# BSPD_-_AMS.net
KiCad netlist of a schematic drawn in Altium Designer
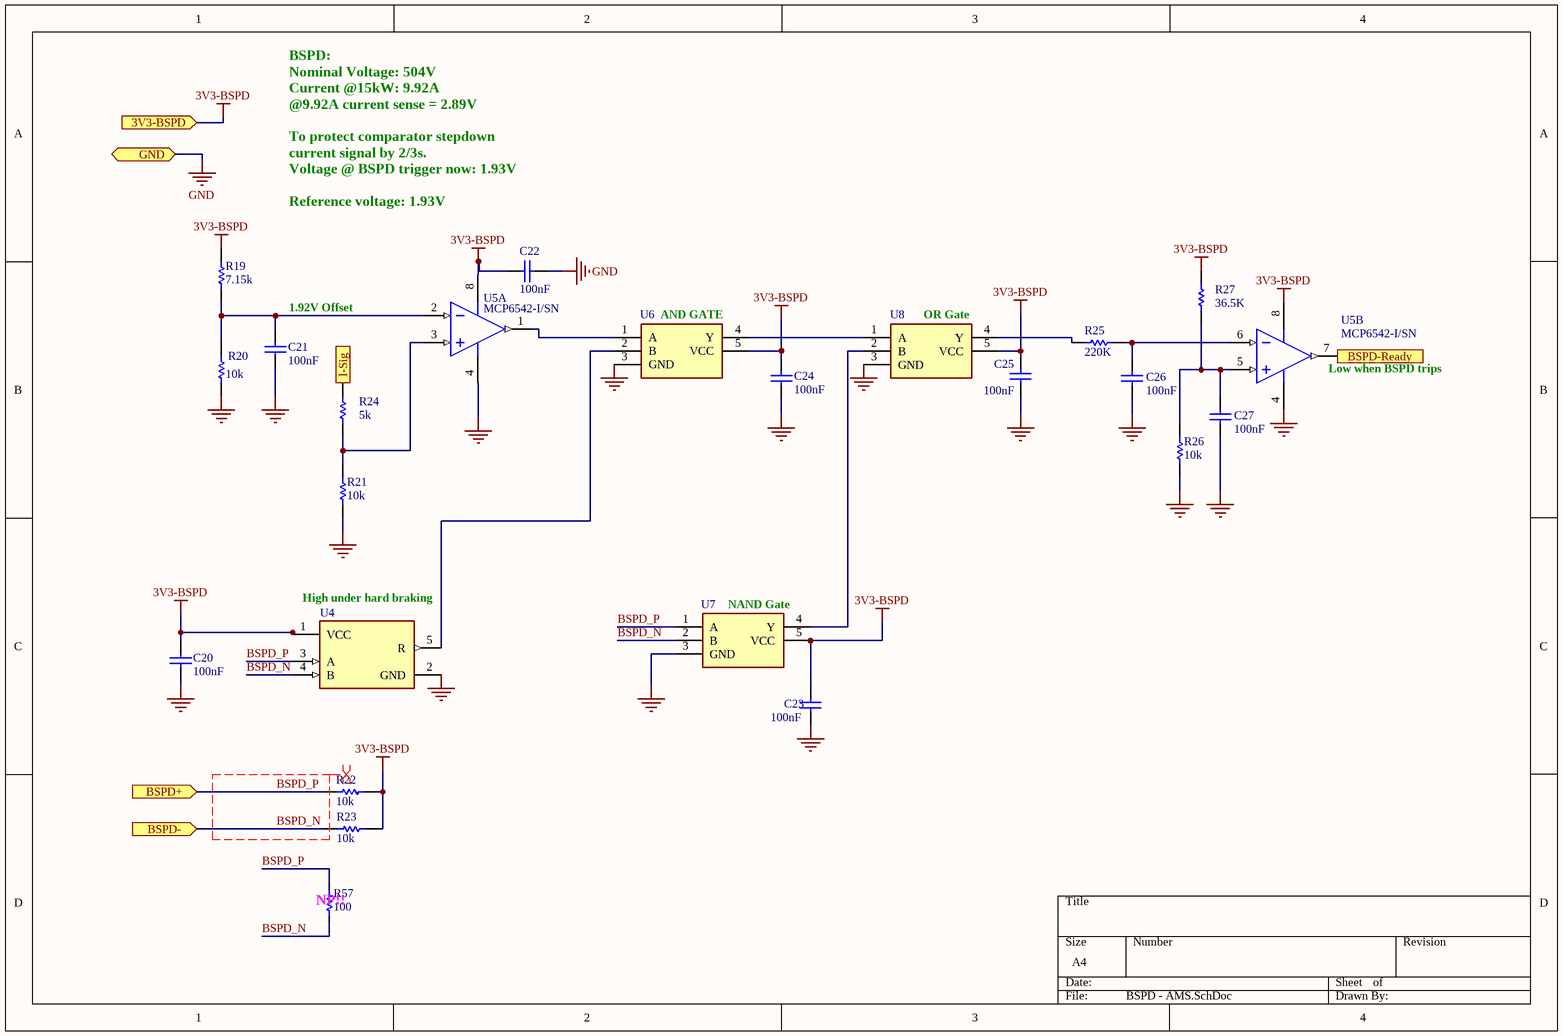
[diagram p0: BSPD - AMS.SchDoc]

(export (version "E")
  (design (tool "Eeschema 10.0.6"))
  (components
    (comp (ref "C20")
      (value "100nF")
      (footprint "CAP0603")
      (description "C0603C104K3RAC7013")
      (fields (field (name "PUBLISHER") "Altium Limited"))
      (libsource (lib "Miscellaneous Devices") (part "Cap"))
    )
    (comp (ref "C21")
      (value "100nF")
      (footprint "CAP0603")
      (description "C0603C104K3RAC7013")
      (fields (field (name "PUBLISHER") "Altium Limited"))
      (libsource (lib "Miscellaneous Devices") (part "Cap"))
    )
    (comp (ref "C22")
      (value "100nF")
      (footprint "CAP0603")
      (description "C0603C104K3RAC7013")
      (fields (field (name "PUBLISHER") "Altium Limited"))
      (libsource (lib "Miscellaneous Devices") (part "Cap"))
    )
    (comp (ref "C23")
      (value "100nF")
      (footprint "CAP0603")
      (description "C0603C104K3RAC7013")
      (fields (field (name "PUBLISHER") "Altium Limited"))
      (libsource (lib "Miscellaneous Devices") (part "Cap"))
    )
    (comp (ref "C24")
      (value "100nF")
      (footprint "CAP0603")
      (description "C0603C104K3RAC7013")
      (fields (field (name "PUBLISHER") "Altium Limited"))
      (libsource (lib "Miscellaneous Devices") (part "Cap"))
    )
    (comp (ref "C25")
      (value "100nF")
      (footprint "CAP0603")
      (description "C0603C104K3RAC7013")
      (fields (field (name "PUBLISHER") "Altium Limited"))
      (libsource (lib "Miscellaneous Devices") (part "Cap"))
    )
    (comp (ref "C26")
      (value "100nF")
      (footprint "CAP0603")
      (description "C0603C104K3RAC7013")
      (fields (field (name "PUBLISHER") "Altium Limited"))
      (libsource (lib "Miscellaneous Devices") (part "Cap"))
    )
    (comp (ref "C27")
      (value "100nF")
      (footprint "CAP0603")
      (description "C0603C104K3RAC7013")
      (fields (field (name "PUBLISHER") "Altium Limited"))
      (libsource (lib "Miscellaneous Devices") (part "Cap"))
    )
    (comp (ref "R19")
      (value "7.15k")
      (footprint "RESC1608X55N")
      (fields (field (name "Comment") "RN73C1J7K15BTDF") (field (name "PUBLISHER") "Altium Limited"))
      (libsource (lib "Miscellaneous Devices") (part "Res1"))
    )
    (comp (ref "R20")
      (value "10k")
      (footprint "RESC1608X55N")
      (fields (field (name "Comment") "RC0603FR-1310KL") (field (name "PUBLISHER") "Altium Limited"))
      (libsource (lib "Miscellaneous Devices") (part "Res1"))
    )
    (comp (ref "R21")
      (value "10k")
      (footprint "RESC1608X55N")
      (fields (field (name "Comment") "RC0603FR-1310KL") (field (name "PUBLISHER") "Altium Limited"))
      (libsource (lib "Miscellaneous Devices") (part "Res1"))
    )
    (comp (ref "R22")
      (value "10k")
      (footprint "RESC1608X55N")
      (description "169-4216")
      (fields (field (name "Comment") "RC0603FR-1310KL") (field (name "PUBLISHER") "Altium Limited"))
      (libsource (lib "Miscellaneous Devices") (part "Res1"))
    )
    (comp (ref "R23")
      (value "10k")
      (footprint "RESC1608X55N")
      (description "169-4216")
      (fields (field (name "Comment") "RC0603FR-1310KL") (field (name "PUBLISHER") "Altium Limited"))
      (libsource (lib "Miscellaneous Devices") (part "Res1"))
    )
    (comp (ref "R24")
      (value "5k")
      (footprint "RESC1608X55N")
      (fields (field (name "Comment") "CR0603AFX-5101EAS") (field (name "PUBLISHER") "Altium Limited"))
      (libsource (lib "Miscellaneous Devices") (part "Res1"))
    )
    (comp (ref "R25")
      (value "220K")
      (footprint "RESC1608X55N")
      (description "Resistor")
      (fields (field (name "Comment") "CRCW0603-220K-E3") (field (name "PUBLISHER") "Altium Limited"))
      (libsource (lib "Miscellaneous Devices") (part "Res1"))
    )
    (comp (ref "R26")
      (value "10k")
      (footprint "RESC1608X55N")
      (description "Resistor")
      (fields (field (name "Comment") "RC0603FR-1310KL") (field (name "PUBLISHER") "Altium Limited"))
      (libsource (lib "Miscellaneous Devices") (part "Res1"))
    )
    (comp (ref "R27")
      (value "36.5K")
      (footprint "RESC1608X55N")
      (description "Resistor")
      (fields (field (name "Comment") "CRCW060336K5FKEAC") (field (name "PUBLISHER") "Altium Limited"))
      (libsource (lib "Miscellaneous Devices") (part "Res1"))
    )
    (comp (ref "R57")
      (value "100")
      (footprint "R-0603")
      (description "NP")
      (fields (field (name "Comment") "Resistor"))
      (libsource (lib "Passives") (part "Resistor"))
    )
    (comp (ref "U4")
      (value "SN65LVDT2DBVT")
      (footprint "FP-DBV0005A-MFG")
      (description "IC RECEIVER 0/1 SOT23-5")
      (fields
        (field (name "OCTOPART") "https://octopart.com/sn65lvdt2dbvt-texas+instruments-712102")
        (field (name "MANUFACTURER") "Texas Instruments")
      )
      (libsource (lib "Altium Content Vault") (part "80154aa7be0093f96882e9a6708b811"))
    )
    (comp (ref "U5")
      (value "MCP6542-I/SN")
      (footprint "SOIC-SN8_N")
      (description "Push-Pull Output Sub-Microamp Comparator, 8-Pin SOIC, Industrial Temperature")
      (libsource (lib "Altium Content Vault") (part "LO-COMP-MCP6542-IL8"))
    )
    (comp (ref "U6")
      (value "SN74LVC1G08MDBVREP")
      (footprint "SOT95P280X145-5N")
      (description "Integrated Circuit")
      (fields (field (name "MOUSER2 PART NUMBER") "595-SN74LVC08MDBVREP"))
      (libsource (lib "SamacSys") (part "SN74LVC1G08MDBVREP"))
    )
    (comp (ref "U7")
      (value "NC7SZ00M5X")
      (footprint "SOT95P280X125-5N")
      (description "NAND GATEEE")
      (fields (field (name "MANUFACTURER_PART_NUMBER") "NC7S02M5X"))
      (libsource (lib "SamacSys") (part "NC7S02M5X"))
    )
    (comp (ref "U8")
      (value "NC7S32M5X")
      (footprint "SOT95P275X110-5N")
      (description "OR GATEEEE")
      (libsource (lib "SamacSys") (part "NC7S32M5X"))
    )
  )
  (nets
    (net (code "1") (name "/BSPD-Ready") (class "Default")
      (node (ref "U5") (pin "7") (pinfunction "OUTB_7") (pintype "output"))
    )
    (net (code "2") (name "/BSPD_N") (class "Default")
      (node (ref "R23") (pin "1") (pinfunction "1_1") (pintype "passive"))
      (node (ref "R57") (pin "1") (pinfunction "1_1") (pintype "passive"))
      (node (ref "U4") (pin "4") (pinfunction "B_4") (pintype "input"))
      (node (ref "U7") (pin "2") (pinfunction "B_2") (pintype "passive"))
    )
    (net (code "3") (name "/BSPD_P") (class "Default")
      (node (ref "R22") (pin "1") (pinfunction "1_1") (pintype "passive"))
      (node (ref "R57") (pin "2") (pinfunction "2_2") (pintype "passive"))
      (node (ref "U4") (pin "3") (pinfunction "A_3") (pintype "input"))
      (node (ref "U7") (pin "1") (pinfunction "A_1") (pintype "passive"))
    )
    (net (code "4") (name "/I-Sig") (class "Default")
      (node (ref "R24") (pin "2") (pinfunction "2_2") (pintype "passive"))
    )
    (net (code "5") (name "3V3-BSPD") (class "Default")
      (node (ref "C20") (pin "2") (pinfunction "2_2") (pintype "passive"))
      (node (ref "C22") (pin "2") (pinfunction "2_2") (pintype "passive"))
      (node (ref "C23") (pin "2") (pinfunction "2_2") (pintype "passive"))
      (node (ref "C24") (pin "2") (pinfunction "2_2") (pintype "passive"))
      (node (ref "C25") (pin "2") (pinfunction "2_2") (pintype "passive"))
      (node (ref "R19") (pin "2") (pinfunction "2_2") (pintype "passive"))
      (node (ref "R22") (pin "2") (pinfunction "2_2") (pintype "passive"))
      (node (ref "R23") (pin "2") (pinfunction "2_2") (pintype "passive"))
      (node (ref "R27") (pin "2") (pinfunction "2_2") (pintype "passive"))
      (node (ref "U4") (pin "1") (pinfunction "VCC_1") (pintype "passive"))
      (node (ref "U5") (pin "8") (pinfunction "VDD_8") (pintype "passive"))
      (node (ref "U6") (pin "5") (pinfunction "VCC_5") (pintype "passive"))
      (node (ref "U7") (pin "5") (pinfunction "VCC_5") (pintype "passive"))
      (node (ref "U8") (pin "5") (pinfunction "VCC_5") (pintype "passive"))
    )
    (net (code "6") (name "GND") (class "Default")
      (node (ref "C20") (pin "1") (pinfunction "1_1") (pintype "passive"))
      (node (ref "C21") (pin "1") (pinfunction "1_1") (pintype "passive"))
      (node (ref "C22") (pin "1") (pinfunction "1_1") (pintype "passive"))
      (node (ref "C23") (pin "1") (pinfunction "1_1") (pintype "passive"))
      (node (ref "C24") (pin "1") (pinfunction "1_1") (pintype "passive"))
      (node (ref "C25") (pin "1") (pinfunction "1_1") (pintype "passive"))
      (node (ref "C26") (pin "1") (pinfunction "1_1") (pintype "passive"))
      (node (ref "C27") (pin "1") (pinfunction "1_1") (pintype "passive"))
      (node (ref "R20") (pin "1") (pinfunction "1_1") (pintype "passive"))
      (node (ref "R21") (pin "1") (pinfunction "1_1") (pintype "passive"))
      (node (ref "R26") (pin "1") (pinfunction "1_1") (pintype "passive"))
      (node (ref "U4") (pin "2") (pinfunction "GND_2") (pintype "passive"))
      (node (ref "U5") (pin "4") (pinfunction "VSS_4") (pintype "power_in"))
      (node (ref "U6") (pin "3") (pinfunction "GND_3") (pintype "passive"))
      (node (ref "U7") (pin "3") (pinfunction "GND_3") (pintype "passive"))
      (node (ref "U8") (pin "3") (pinfunction "GND_3") (pintype "passive"))
    )
    (net (code "7") (name "Net-(U4-R)") (class "Default")
      (node (ref "U4") (pin "5") (pinfunction "R_5") (pintype "output"))
      (node (ref "U6") (pin "2") (pinfunction "B_2") (pintype "passive"))
    )
    (net (code "8") (name "Net-(U5A-OUTA)") (class "Default")
      (node (ref "U5") (pin "1") (pinfunction "OUTA_1") (pintype "output"))
      (node (ref "U6") (pin "1") (pinfunction "A_1") (pintype "passive"))
    )
    (net (code "9") (name "Net-(U5A-VINA+)") (class "Default")
      (node (ref "R21") (pin "2") (pinfunction "2_2") (pintype "passive"))
      (node (ref "R24") (pin "1") (pinfunction "1_1") (pintype "passive"))
      (node (ref "U5") (pin "3") (pinfunction "VINA+_3") (pintype "input"))
    )
    (net (code "10") (name "Net-(U5A-VINA-)") (class "Default")
      (node (ref "C21") (pin "2") (pinfunction "2_2") (pintype "passive"))
      (node (ref "R19") (pin "1") (pinfunction "1_1") (pintype "passive"))
      (node (ref "R20") (pin "2") (pinfunction "2_2") (pintype "passive"))
      (node (ref "U5") (pin "2") (pinfunction "VINA-_2") (pintype "input"))
    )
    (net (code "11") (name "Net-(U5B-VINB+)") (class "Default")
      (node (ref "C27") (pin "2") (pinfunction "2_2") (pintype "passive"))
      (node (ref "R26") (pin "2") (pinfunction "2_2") (pintype "passive"))
      (node (ref "R27") (pin "1") (pinfunction "1_1") (pintype "passive"))
      (node (ref "U5") (pin "5") (pinfunction "VINB+_5") (pintype "input"))
    )
    (net (code "12") (name "Net-(U5B-VINB-)") (class "Default")
      (node (ref "C26") (pin "2") (pinfunction "2_2") (pintype "passive"))
      (node (ref "R25") (pin "1") (pinfunction "1_1") (pintype "passive"))
      (node (ref "U5") (pin "6") (pinfunction "VINB-_6") (pintype "input"))
    )
    (net (code "13") (name "Net-(U6-Y)") (class "Default")
      (node (ref "U6") (pin "4") (pinfunction "Y_4") (pintype "passive"))
      (node (ref "U8") (pin "1") (pinfunction "A_1") (pintype "passive"))
    )
    (net (code "14") (name "Net-(U7-Y)") (class "Default")
      (node (ref "U7") (pin "4") (pinfunction "Y_4") (pintype "passive"))
      (node (ref "U8") (pin "2") (pinfunction "B_2") (pintype "passive"))
    )
    (net (code "15") (name "Net-(U8-Y)") (class "Default")
      (node (ref "R25") (pin "2") (pinfunction "2_2") (pintype "passive"))
      (node (ref "U8") (pin "4") (pinfunction "Y_4") (pintype "passive"))
    )
  )
)
